# Translators.net
KiCad netlist of a schematic drawn in Altium Designer
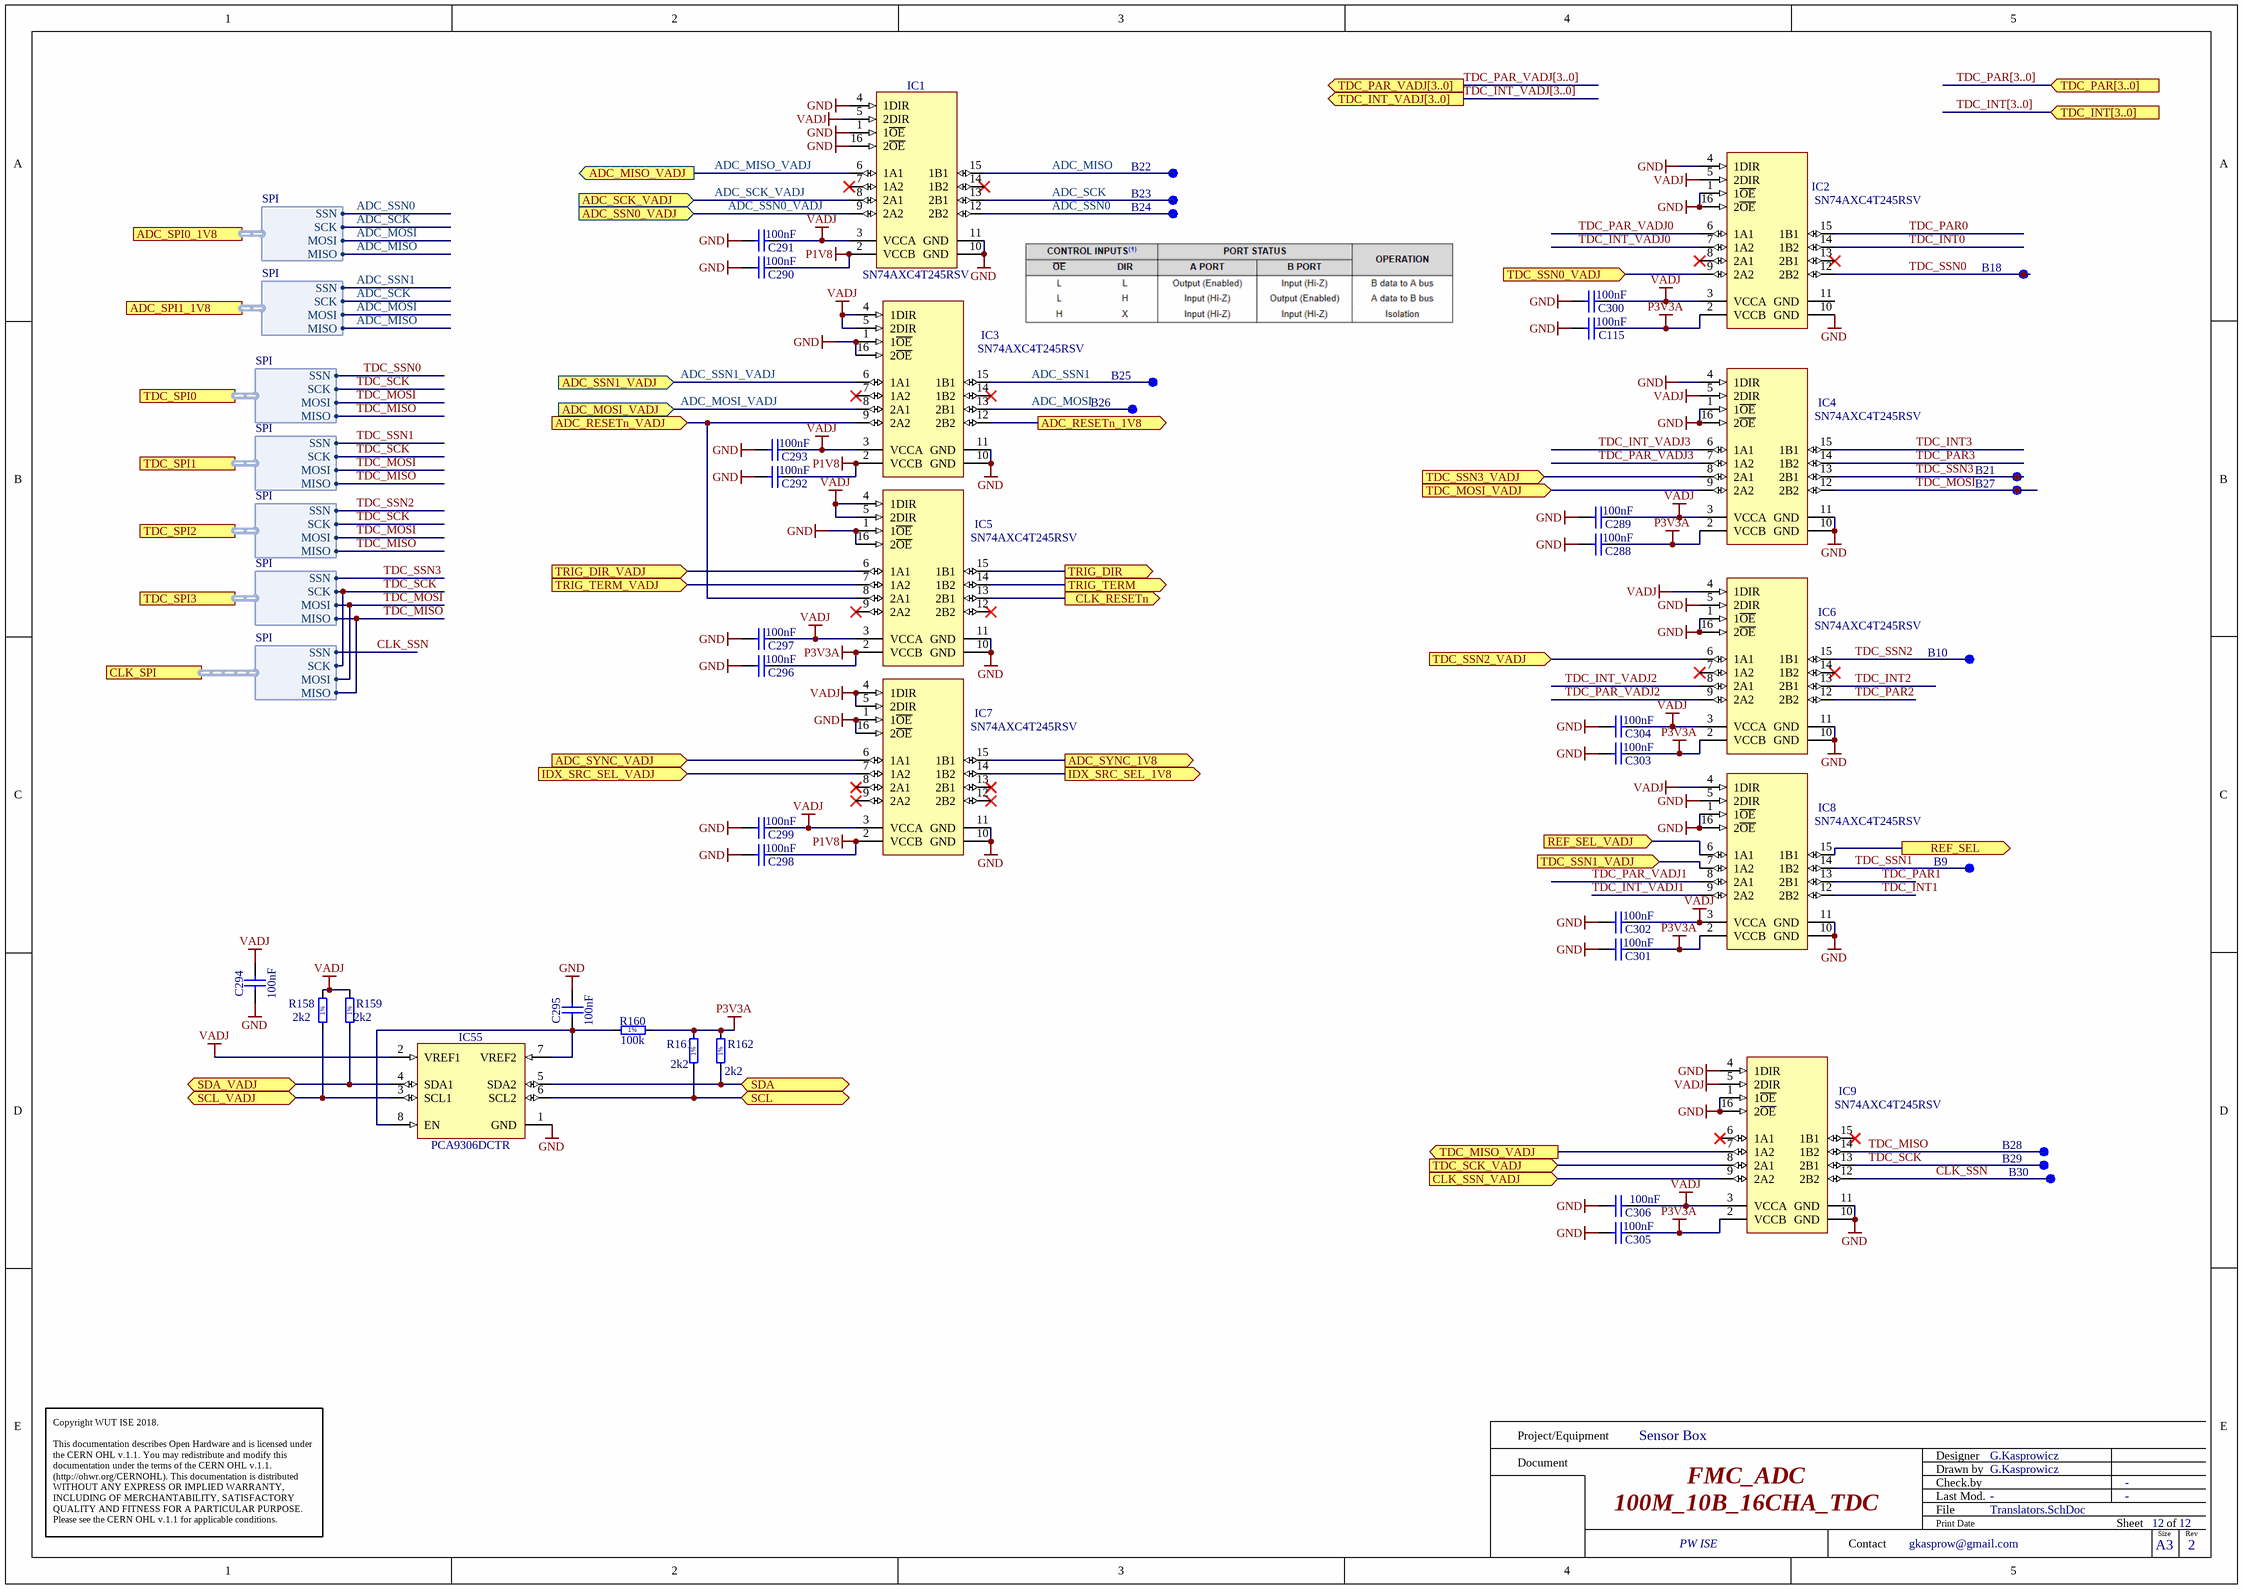
[diagram p0: Translators.SchDoc]

(export (version "E")
  (design (tool "Eeschema 10.0.6"))
  (components
    (comp (ref "B9")
      (value "SMD Pad")
      (footprint "C100")
      (description "Through Hole Pad")
      (fields (field (name "PART NUMBER") "SMD_PAD_D1MM") (field (name "AUTHOR") "CERN DEM JLC"))
      (libsource (lib "Eletro-mechanical") (part "Single SMD Pad (Round)"))
    )
    (comp (ref "B10")
      (value "SMD Pad")
      (footprint "C100")
      (description "Through Hole Pad")
      (fields (field (name "PART NUMBER") "SMD_PAD_D1MM") (field (name "AUTHOR") "CERN DEM JLC"))
      (libsource (lib "Eletro-mechanical") (part "Single SMD Pad (Round)"))
    )
    (comp (ref "B18")
      (value "SMD Pad")
      (footprint "C100")
      (description "Through Hole Pad")
      (fields (field (name "PART NUMBER") "SMD_PAD_D1MM") (field (name "AUTHOR") "CERN DEM JLC"))
      (libsource (lib "Eletro-mechanical") (part "Single SMD Pad (Round)"))
    )
    (comp (ref "B21")
      (value "SMD Pad")
      (footprint "C100")
      (description "Through Hole Pad")
      (fields (field (name "PART NUMBER") "SMD_PAD_D1MM") (field (name "AUTHOR") "CERN DEM JLC"))
      (libsource (lib "Eletro-mechanical") (part "Single SMD Pad (Round)"))
    )
    (comp (ref "B22")
      (value "SMD Pad")
      (footprint "C100")
      (description "Through Hole Pad")
      (fields (field (name "PART NUMBER") "SMD_PAD_D1MM") (field (name "AUTHOR") "CERN DEM JLC"))
      (libsource (lib "Eletro-mechanical") (part "Single SMD Pad (Round)"))
    )
    (comp (ref "B23")
      (value "SMD Pad")
      (footprint "C100")
      (description "Through Hole Pad")
      (fields (field (name "PART NUMBER") "SMD_PAD_D1MM") (field (name "AUTHOR") "CERN DEM JLC"))
      (libsource (lib "Eletro-mechanical") (part "Single SMD Pad (Round)"))
    )
    (comp (ref "B24")
      (value "SMD Pad")
      (footprint "C100")
      (description "Through Hole Pad")
      (fields (field (name "PART NUMBER") "SMD_PAD_D1MM") (field (name "AUTHOR") "CERN DEM JLC"))
      (libsource (lib "Eletro-mechanical") (part "Single SMD Pad (Round)"))
    )
    (comp (ref "B25")
      (value "SMD Pad")
      (footprint "C100")
      (description "Through Hole Pad")
      (fields (field (name "PART NUMBER") "SMD_PAD_D1MM") (field (name "AUTHOR") "CERN DEM JLC"))
      (libsource (lib "Eletro-mechanical") (part "Single SMD Pad (Round)"))
    )
    (comp (ref "B26")
      (value "SMD Pad")
      (footprint "C100")
      (description "Through Hole Pad")
      (fields (field (name "PART NUMBER") "SMD_PAD_D1MM") (field (name "AUTHOR") "CERN DEM JLC"))
      (libsource (lib "Eletro-mechanical") (part "Single SMD Pad (Round)"))
    )
    (comp (ref "B27")
      (value "SMD Pad")
      (footprint "C100")
      (description "Through Hole Pad")
      (fields (field (name "PART NUMBER") "SMD_PAD_D1MM") (field (name "AUTHOR") "CERN DEM JLC"))
      (libsource (lib "Eletro-mechanical") (part "Single SMD Pad (Round)"))
    )
    (comp (ref "B28")
      (value "SMD Pad")
      (footprint "C100")
      (description "Through Hole Pad")
      (fields (field (name "PART NUMBER") "SMD_PAD_D1MM") (field (name "AUTHOR") "CERN DEM JLC"))
      (libsource (lib "Eletro-mechanical") (part "Single SMD Pad (Round)"))
    )
    (comp (ref "B29")
      (value "SMD Pad")
      (footprint "C100")
      (description "Through Hole Pad")
      (fields (field (name "PART NUMBER") "SMD_PAD_D1MM") (field (name "AUTHOR") "CERN DEM JLC"))
      (libsource (lib "Eletro-mechanical") (part "Single SMD Pad (Round)"))
    )
    (comp (ref "B30")
      (value "SMD Pad")
      (footprint "C100")
      (description "Through Hole Pad")
      (fields (field (name "PART NUMBER") "SMD_PAD_D1MM") (field (name "AUTHOR") "CERN DEM JLC"))
      (libsource (lib "Eletro-mechanical") (part "Single SMD Pad (Round)"))
    )
    (comp (ref "C115")
      (value "100nF")
      (footprint "CAPC0603X33N")
      (description "Non-polarised capacitor")
      (fields
        (field (name "MANUFACTURER PART NUMBER") "CC0201_100NF_6.3V_10%_X5R")
        (field (name "MANUFACTURER") "GENERIC")
        (field (name "AUTHOR") "CERN DEM JLC")
      )
      (libsource (lib "Capacitors") (part "Capacitor - non polarized"))
    )
    (comp (ref "C288")
      (value "100nF")
      (footprint "CAPC0603X33N")
      (description "Non-polarised capacitor")
      (fields
        (field (name "MANUFACTURER PART NUMBER") "CC0201_100NF_6.3V_10%_X5R")
        (field (name "MANUFACTURER") "GENERIC")
        (field (name "AUTHOR") "CERN DEM JLC")
      )
      (libsource (lib "Capacitors") (part "Capacitor - non polarized"))
    )
    (comp (ref "C289")
      (value "100nF")
      (footprint "CAPC0603X33N")
      (description "Non-polarised capacitor")
      (fields
        (field (name "MANUFACTURER PART NUMBER") "CC0201_100NF_6.3V_10%_X5R")
        (field (name "MANUFACTURER") "GENERIC")
        (field (name "AUTHOR") "CERN DEM JLC")
      )
      (libsource (lib "Capacitors") (part "Capacitor - non polarized"))
    )
    (comp (ref "C290")
      (value "100nF")
      (footprint "CAPC0603X33N")
      (description "Non-polarised capacitor")
      (fields
        (field (name "MANUFACTURER PART NUMBER") "CC0201_100NF_6.3V_10%_X5R")
        (field (name "MANUFACTURER") "GENERIC")
        (field (name "AUTHOR") "CERN DEM JLC")
      )
      (libsource (lib "Capacitors") (part "Capacitor - non polarized"))
    )
    (comp (ref "C291")
      (value "100nF")
      (footprint "CAPC0603X33N")
      (description "Non-polarised capacitor")
      (fields
        (field (name "MANUFACTURER PART NUMBER") "CC0201_100NF_6.3V_10%_X5R")
        (field (name "MANUFACTURER") "GENERIC")
        (field (name "AUTHOR") "CERN DEM JLC")
      )
      (libsource (lib "Capacitors") (part "Capacitor - non polarized"))
    )
    (comp (ref "C292")
      (value "100nF")
      (footprint "CAPC0603X33N")
      (description "Non-polarised capacitor")
      (fields
        (field (name "MANUFACTURER PART NUMBER") "CC0201_100NF_6.3V_10%_X5R")
        (field (name "MANUFACTURER") "GENERIC")
        (field (name "AUTHOR") "CERN DEM JLC")
      )
      (libsource (lib "Capacitors") (part "Capacitor - non polarized"))
    )
    (comp (ref "C293")
      (value "100nF")
      (footprint "CAPC0603X33N")
      (description "Non-polarised capacitor")
      (fields
        (field (name "MANUFACTURER PART NUMBER") "CC0201_100NF_6.3V_10%_X5R")
        (field (name "MANUFACTURER") "GENERIC")
        (field (name "AUTHOR") "CERN DEM JLC")
      )
      (libsource (lib "Capacitors") (part "Capacitor - non polarized"))
    )
    (comp (ref "C294")
      (value "100nF")
      (footprint "CAPC0603X33N")
      (description "Non-polarised capacitor")
      (fields
        (field (name "MANUFACTURER PART NUMBER") "CC0201_100NF_6.3V_10%_X5R")
        (field (name "MANUFACTURER") "GENERIC")
        (field (name "AUTHOR") "CERN DEM JLC")
      )
      (libsource (lib "Capacitors") (part "Capacitor - non polarized"))
    )
    (comp (ref "C295")
      (value "100nF")
      (footprint "CAPC0603X33N")
      (description "Non-polarised capacitor")
      (fields
        (field (name "MANUFACTURER PART NUMBER") "CC0201_100NF_6.3V_10%_X5R")
        (field (name "MANUFACTURER") "GENERIC")
        (field (name "AUTHOR") "CERN DEM JLC")
      )
      (libsource (lib "Capacitors") (part "Capacitor - non polarized"))
    )
    (comp (ref "C296")
      (value "100nF")
      (footprint "CAPC0603X33N")
      (description "Non-polarised capacitor")
      (fields
        (field (name "MANUFACTURER PART NUMBER") "CC0201_100NF_6.3V_10%_X5R")
        (field (name "MANUFACTURER") "GENERIC")
        (field (name "AUTHOR") "CERN DEM JLC")
      )
      (libsource (lib "Capacitors") (part "Capacitor - non polarized"))
    )
    (comp (ref "C297")
      (value "100nF")
      (footprint "CAPC0603X33N")
      (description "Non-polarised capacitor")
      (fields
        (field (name "MANUFACTURER PART NUMBER") "CC0201_100NF_6.3V_10%_X5R")
        (field (name "MANUFACTURER") "GENERIC")
        (field (name "AUTHOR") "CERN DEM JLC")
      )
      (libsource (lib "Capacitors") (part "Capacitor - non polarized"))
    )
    (comp (ref "C298")
      (value "100nF")
      (footprint "CAPC0603X33N")
      (description "Non-polarised capacitor")
      (fields
        (field (name "MANUFACTURER PART NUMBER") "CC0201_100NF_6.3V_10%_X5R")
        (field (name "MANUFACTURER") "GENERIC")
        (field (name "AUTHOR") "CERN DEM JLC")
      )
      (libsource (lib "Capacitors") (part "Capacitor - non polarized"))
    )
    (comp (ref "C299")
      (value "100nF")
      (footprint "CAPC0603X33N")
      (description "Non-polarised capacitor")
      (fields
        (field (name "MANUFACTURER PART NUMBER") "CC0201_100NF_6.3V_10%_X5R")
        (field (name "MANUFACTURER") "GENERIC")
        (field (name "AUTHOR") "CERN DEM JLC")
      )
      (libsource (lib "Capacitors") (part "Capacitor - non polarized"))
    )
    (comp (ref "C300")
      (value "100nF")
      (footprint "CAPC0603X33N")
      (description "Non-polarised capacitor")
      (fields
        (field (name "MANUFACTURER PART NUMBER") "CC0201_100NF_6.3V_10%_X5R")
        (field (name "MANUFACTURER") "GENERIC")
        (field (name "AUTHOR") "CERN DEM JLC")
      )
      (libsource (lib "Capacitors") (part "Capacitor - non polarized"))
    )
    (comp (ref "C301")
      (value "100nF")
      (footprint "CAPC0603X33N")
      (description "Non-polarised capacitor")
      (fields
        (field (name "MANUFACTURER PART NUMBER") "CC0201_100NF_6.3V_10%_X5R")
        (field (name "MANUFACTURER") "GENERIC")
        (field (name "AUTHOR") "CERN DEM JLC")
      )
      (libsource (lib "Capacitors") (part "Capacitor - non polarized"))
    )
    (comp (ref "C302")
      (value "100nF")
      (footprint "CAPC0603X33N")
      (description "Non-polarised capacitor")
      (fields
        (field (name "MANUFACTURER PART NUMBER") "CC0201_100NF_6.3V_10%_X5R")
        (field (name "MANUFACTURER") "GENERIC")
        (field (name "AUTHOR") "CERN DEM JLC")
      )
      (libsource (lib "Capacitors") (part "Capacitor - non polarized"))
    )
    (comp (ref "C303")
      (value "100nF")
      (footprint "CAPC0603X33N")
      (description "Non-polarised capacitor")
      (fields
        (field (name "MANUFACTURER PART NUMBER") "CC0201_100NF_6.3V_10%_X5R")
        (field (name "MANUFACTURER") "GENERIC")
        (field (name "AUTHOR") "CERN DEM JLC")
      )
      (libsource (lib "Capacitors") (part "Capacitor - non polarized"))
    )
    (comp (ref "C304")
      (value "100nF")
      (footprint "CAPC0603X33N")
      (description "Non-polarised capacitor")
      (fields
        (field (name "MANUFACTURER PART NUMBER") "CC0201_100NF_6.3V_10%_X5R")
        (field (name "MANUFACTURER") "GENERIC")
        (field (name "AUTHOR") "CERN DEM JLC")
      )
      (libsource (lib "Capacitors") (part "Capacitor - non polarized"))
    )
    (comp (ref "C305")
      (value "100nF")
      (footprint "CAPC0603X33N")
      (description "Non-polarised capacitor")
      (fields
        (field (name "MANUFACTURER PART NUMBER") "CC0201_100NF_6.3V_10%_X5R")
        (field (name "MANUFACTURER") "GENERIC")
        (field (name "AUTHOR") "CERN DEM JLC")
      )
      (libsource (lib "Capacitors") (part "Capacitor - non polarized"))
    )
    (comp (ref "C306")
      (value "100nF")
      (footprint "CAPC0603X33N")
      (description "Non-polarised capacitor")
      (fields
        (field (name "MANUFACTURER PART NUMBER") "CC0201_100NF_6.3V_10%_X5R")
        (field (name "MANUFACTURER") "GENERIC")
        (field (name "AUTHOR") "CERN DEM JLC")
      )
      (libsource (lib "Capacitors") (part "Capacitor - non polarized"))
    )
    (comp (ref "IC1")
      (value "SN74AXC4T245RSV")
      (footprint "QFN40P180X260X55-16N")
      (description "4-Bit Dual-Supply Bus Transceiver with Configurable Voltage Translation and 3-State Output")
      (fields (field (name "MANUFACTURER") "TEXAS INSTRUMENTS") (field (name "AUTHOR") "GK"))
      (libsource (lib "ICS-logic") (part "SN74AXC4T245"))
    )
    (comp (ref "IC2")
      (value "SN74AXC4T245RSV")
      (footprint "QFN40P180X260X55-16N")
      (description "4-Bit Dual-Supply Bus Transceiver with Configurable Voltage Translation and 3-State Output")
      (fields (field (name "MANUFACTURER") "TEXAS INSTRUMENTS") (field (name "AUTHOR") "GK"))
      (libsource (lib "ICS-logic") (part "SN74AXC4T245"))
    )
    (comp (ref "IC3")
      (value "SN74AXC4T245RSV")
      (footprint "QFN40P180X260X55-16N")
      (description "4-Bit Dual-Supply Bus Transceiver with Configurable Voltage Translation and 3-State Output")
      (fields (field (name "MANUFACTURER") "TEXAS INSTRUMENTS") (field (name "AUTHOR") "GK"))
      (libsource (lib "ICS-logic") (part "SN74AXC4T245"))
    )
    (comp (ref "IC4")
      (value "SN74AXC4T245RSV")
      (footprint "QFN40P180X260X55-16N")
      (description "4-Bit Dual-Supply Bus Transceiver with Configurable Voltage Translation and 3-State Output")
      (fields (field (name "MANUFACTURER") "TEXAS INSTRUMENTS") (field (name "AUTHOR") "GK"))
      (libsource (lib "ICS-logic") (part "SN74AXC4T245"))
    )
    (comp (ref "IC5")
      (value "SN74AXC4T245RSV")
      (footprint "QFN40P180X260X55-16N")
      (description "4-Bit Dual-Supply Bus Transceiver with Configurable Voltage Translation and 3-State Output")
      (fields (field (name "MANUFACTURER") "TEXAS INSTRUMENTS") (field (name "AUTHOR") "GK"))
      (libsource (lib "ICS-logic") (part "SN74AXC4T245"))
    )
    (comp (ref "IC6")
      (value "SN74AXC4T245RSV")
      (footprint "QFN40P180X260X55-16N")
      (description "4-Bit Dual-Supply Bus Transceiver with Configurable Voltage Translation and 3-State Output")
      (fields (field (name "MANUFACTURER") "TEXAS INSTRUMENTS") (field (name "AUTHOR") "GK"))
      (libsource (lib "ICS-logic") (part "SN74AXC4T245"))
    )
    (comp (ref "IC7")
      (value "SN74AXC4T245RSV")
      (footprint "QFN40P180X260X55-16N")
      (description "4-Bit Dual-Supply Bus Transceiver with Configurable Voltage Translation and 3-State Output")
      (fields (field (name "MANUFACTURER") "TEXAS INSTRUMENTS") (field (name "AUTHOR") "GK"))
      (libsource (lib "ICS-logic") (part "SN74AXC4T245"))
    )
    (comp (ref "IC8")
      (value "SN74AXC4T245RSV")
      (footprint "QFN40P180X260X55-16N")
      (description "4-Bit Dual-Supply Bus Transceiver with Configurable Voltage Translation and 3-State Output")
      (fields (field (name "MANUFACTURER") "TEXAS INSTRUMENTS") (field (name "AUTHOR") "GK"))
      (libsource (lib "ICS-logic") (part "SN74AXC4T245"))
    )
    (comp (ref "IC9")
      (value "SN74AXC4T245RSV")
      (footprint "QFN40P180X260X55-16N")
      (description "4-Bit Dual-Supply Bus Transceiver with Configurable Voltage Translation and 3-State Output")
      (fields (field (name "MANUFACTURER") "TEXAS INSTRUMENTS") (field (name "AUTHOR") "GK"))
      (libsource (lib "ICS-logic") (part "SN74AXC4T245"))
    )
    (comp (ref "IC55")
      (value "PCA9306DCTR")
      (footprint "SOP65P400X130-8N")
      (description "Dual Bidirectional I2C Bus And SMBus Voltage-Level Translator")
      (fields (field (name "MANUFACTURER") "TEXAS INSTRUMENTS") (field (name "AUTHOR") "CERN DEM JLC"))
      (libsource (lib "ICs And Semiconductors") (part "PCA9306DC"))
    )
    (comp (ref "R158")
      (value "2k2")
      (footprint "RESC1005X40N")
      (description "Resistor - 1%")
      (fields
        (field (name "PART NUMBER") "R0402_2K2_1%_0.0625W_100PPM")
        (field (name "POWER") "0.0625W")
        (field (name "AUTHOR") "CERN DEM JLC")
      )
      (libsource (lib "Resistors") (part "Resistor - 1%"))
    )
    (comp (ref "R159")
      (value "2k2")
      (footprint "RESC1005X40N")
      (description "Resistor - 1%")
      (fields
        (field (name "PART NUMBER") "R0402_2K2_1%_0.0625W_100PPM")
        (field (name "POWER") "0.0625W")
        (field (name "AUTHOR") "CERN DEM JLC")
      )
      (libsource (lib "Resistors") (part "Resistor - 1%"))
    )
    (comp (ref "R160")
      (value "100k")
      (footprint "RESC1005X40N")
      (description "Resistor - 1%")
      (fields
        (field (name "PART NUMBER") "R0402_100K_1%_0.0625W_100PPM")
        (field (name "POWER") "0.0625W")
        (field (name "AUTHOR") "CERN DEM JLC")
      )
      (libsource (lib "Resistors") (part "Resistor - 1%"))
    )
    (comp (ref "R161")
      (value "2k2")
      (footprint "RESC1005X40N")
      (description "Resistor - 1%")
      (fields
        (field (name "PART NUMBER") "R0402_2K2_1%_0.0625W_100PPM")
        (field (name "POWER") "0.0625W")
        (field (name "AUTHOR") "CERN DEM JLC")
      )
      (libsource (lib "Resistors") (part "Resistor - 1%"))
    )
    (comp (ref "R162")
      (value "2k2")
      (footprint "RESC1005X40N")
      (description "Resistor - 1%")
      (fields
        (field (name "PART NUMBER") "R0402_2K2_1%_0.0625W_100PPM")
        (field (name "POWER") "0.0625W")
        (field (name "AUTHOR") "CERN DEM JLC")
      )
      (libsource (lib "Resistors") (part "Resistor - 1%"))
    )
  )
  (nets
    (net (code "2") (name "/ADC_MISO") (class "Default")
      (node (ref "B22") (pin "1") (pinfunction "1_1") (pintype "bidirectional"))
      (node (ref "IC1") (pin "15") (pinfunction "1B1_15") (pintype "bidirectional"))
    )
    (net (code "3") (name "/ADC_MISO_VADJ") (class "Default")
      (node (ref "IC1") (pin "6") (pinfunction "1A1_6") (pintype "bidirectional"))
    )
    (net (code "4") (name "/ADC_MOSI") (class "Default")
      (node (ref "B26") (pin "1") (pinfunction "1_1") (pintype "bidirectional"))
      (node (ref "IC3") (pin "13") (pinfunction "2B1_13") (pintype "bidirectional"))
    )
    (net (code "5") (name "/ADC_MOSI_VADJ") (class "Default")
      (node (ref "IC3") (pin "8") (pinfunction "2A1_8") (pintype "bidirectional"))
    )
    (net (code "6") (name "/ADC_RESETn_1V8") (class "Default")
      (node (ref "IC3") (pin "12") (pinfunction "2B2_12") (pintype "bidirectional"))
    )
    (net (code "7") (name "/ADC_RESETn_VADJ") (class "Default")
      (node (ref "IC3") (pin "9") (pinfunction "2A2_9") (pintype "bidirectional"))
      (node (ref "IC5") (pin "8") (pinfunction "2A1_8") (pintype "bidirectional"))
    )
    (net (code "8") (name "/ADC_SCK") (class "Default")
      (node (ref "B23") (pin "1") (pinfunction "1_1") (pintype "bidirectional"))
      (node (ref "IC1") (pin "13") (pinfunction "2B1_13") (pintype "bidirectional"))
    )
    (net (code "9") (name "/ADC_SCK_VADJ") (class "Default")
      (node (ref "IC1") (pin "8") (pinfunction "2A1_8") (pintype "bidirectional"))
    )
    (net (code "10") (name "/ADC_SSN0") (class "Default")
      (node (ref "B24") (pin "1") (pinfunction "1_1") (pintype "bidirectional"))
      (node (ref "IC1") (pin "12") (pinfunction "2B2_12") (pintype "bidirectional"))
    )
    (net (code "11") (name "/ADC_SSN0_VADJ") (class "Default")
      (node (ref "IC1") (pin "9") (pinfunction "2A2_9") (pintype "bidirectional"))
    )
    (net (code "12") (name "/ADC_SSN1") (class "Default")
      (node (ref "B25") (pin "1") (pinfunction "1_1") (pintype "bidirectional"))
      (node (ref "IC3") (pin "15") (pinfunction "1B1_15") (pintype "bidirectional"))
    )
    (net (code "13") (name "/ADC_SSN1_VADJ") (class "Default")
      (node (ref "IC3") (pin "6") (pinfunction "1A1_6") (pintype "bidirectional"))
    )
    (net (code "14") (name "/ADC_SYNC_1V8") (class "Default")
      (node (ref "IC7") (pin "15") (pinfunction "1B1_15") (pintype "bidirectional"))
    )
    (net (code "15") (name "/ADC_SYNC_VADJ") (class "Default")
      (node (ref "IC7") (pin "6") (pinfunction "1A1_6") (pintype "bidirectional"))
    )
    (net (code "16") (name "/CLK_RESETn") (class "Default")
      (node (ref "IC5") (pin "13") (pinfunction "2B1_13") (pintype "bidirectional"))
    )
    (net (code "17") (name "/CLK_SSN") (class "Default")
      (node (ref "B30") (pin "1") (pinfunction "1_1") (pintype "bidirectional"))
      (node (ref "IC9") (pin "12") (pinfunction "2B2_12") (pintype "bidirectional"))
    )
    (net (code "18") (name "/CLK_SSN_VADJ") (class "Default")
      (node (ref "IC9") (pin "9") (pinfunction "2A2_9") (pintype "bidirectional"))
    )
    (net (code "19") (name "/IDX_SRC_SEL_1V8") (class "Default")
      (node (ref "IC7") (pin "14") (pinfunction "1B2_14") (pintype "bidirectional"))
    )
    (net (code "20") (name "/IDX_SRC_SEL_VADJ") (class "Default")
      (node (ref "IC7") (pin "7") (pinfunction "1A2_7") (pintype "bidirectional"))
    )
    (net (code "21") (name "/REF_SEL") (class "Default")
      (node (ref "IC8") (pin "15") (pinfunction "1B1_15") (pintype "bidirectional"))
    )
    (net (code "22") (name "/REF_SEL_VADJ") (class "Default")
      (node (ref "IC8") (pin "6") (pinfunction "1A1_6") (pintype "bidirectional"))
    )
    (net (code "23") (name "/SCL") (class "Default")
      (node (ref "IC55") (pin "6") (pinfunction "SCL2_6") (pintype "bidirectional"))
      (node (ref "R161") (pin "1") (pinfunction "1_1") (pintype "passive"))
    )
    (net (code "24") (name "/SCL_VADJ") (class "Default")
      (node (ref "IC55") (pin "3") (pinfunction "SCL1_3") (pintype "bidirectional"))
      (node (ref "R158") (pin "1") (pinfunction "1_1") (pintype "passive"))
    )
    (net (code "25") (name "/SDA") (class "Default")
      (node (ref "IC55") (pin "5") (pinfunction "SDA2_5") (pintype "bidirectional"))
      (node (ref "R162") (pin "1") (pinfunction "1_1") (pintype "passive"))
    )
    (net (code "26") (name "/SDA_VADJ") (class "Default")
      (node (ref "IC55") (pin "4") (pinfunction "SDA1_4") (pintype "bidirectional"))
      (node (ref "R159") (pin "1") (pinfunction "1_1") (pintype "passive"))
    )
    (net (code "27") (name "/TDC_INT0") (class "Default")
      (node (ref "IC2") (pin "14") (pinfunction "1B2_14") (pintype "bidirectional"))
    )
    (net (code "28") (name "/TDC_INT1") (class "Default")
      (node (ref "IC8") (pin "12") (pinfunction "2B2_12") (pintype "bidirectional"))
    )
    (net (code "29") (name "/TDC_INT2") (class "Default")
      (node (ref "IC6") (pin "13") (pinfunction "2B1_13") (pintype "bidirectional"))
    )
    (net (code "30") (name "/TDC_INT3") (class "Default")
      (node (ref "IC4") (pin "15") (pinfunction "1B1_15") (pintype "bidirectional"))
    )
    (net (code "32") (name "/TDC_INT_VADJ0") (class "Default")
      (node (ref "IC2") (pin "7") (pinfunction "1A2_7") (pintype "bidirectional"))
    )
    (net (code "33") (name "/TDC_INT_VADJ1") (class "Default")
      (node (ref "IC8") (pin "9") (pinfunction "2A2_9") (pintype "bidirectional"))
    )
    (net (code "34") (name "/TDC_INT_VADJ2") (class "Default")
      (node (ref "IC6") (pin "8") (pinfunction "2A1_8") (pintype "bidirectional"))
    )
    (net (code "35") (name "/TDC_INT_VADJ3") (class "Default")
      (node (ref "IC4") (pin "6") (pinfunction "1A1_6") (pintype "bidirectional"))
    )
    (net (code "37") (name "/TDC_MISO") (class "Default")
      (node (ref "B28") (pin "1") (pinfunction "1_1") (pintype "bidirectional"))
      (node (ref "IC9") (pin "14") (pinfunction "1B2_14") (pintype "bidirectional"))
    )
    (net (code "38") (name "/TDC_MISO_VADJ") (class "Default")
      (node (ref "IC9") (pin "7") (pinfunction "1A2_7") (pintype "bidirectional"))
    )
    (net (code "39") (name "/TDC_MOSI") (class "Default")
      (node (ref "B27") (pin "1") (pinfunction "1_1") (pintype "bidirectional"))
      (node (ref "IC4") (pin "12") (pinfunction "2B2_12") (pintype "bidirectional"))
    )
    (net (code "40") (name "/TDC_MOSI_VADJ") (class "Default")
      (node (ref "IC4") (pin "9") (pinfunction "2A2_9") (pintype "bidirectional"))
    )
    (net (code "41") (name "/TDC_PAR0") (class "Default")
      (node (ref "IC2") (pin "15") (pinfunction "1B1_15") (pintype "bidirectional"))
    )
    (net (code "42") (name "/TDC_PAR1") (class "Default")
      (node (ref "IC8") (pin "13") (pinfunction "2B1_13") (pintype "bidirectional"))
    )
    (net (code "43") (name "/TDC_PAR2") (class "Default")
      (node (ref "IC6") (pin "12") (pinfunction "2B2_12") (pintype "bidirectional"))
    )
    (net (code "44") (name "/TDC_PAR3") (class "Default")
      (node (ref "IC4") (pin "14") (pinfunction "1B2_14") (pintype "bidirectional"))
    )
    (net (code "46") (name "/TDC_PAR_VADJ0") (class "Default")
      (node (ref "IC2") (pin "6") (pinfunction "1A1_6") (pintype "bidirectional"))
    )
    (net (code "47") (name "/TDC_PAR_VADJ1") (class "Default")
      (node (ref "IC8") (pin "8") (pinfunction "2A1_8") (pintype "bidirectional"))
    )
    (net (code "48") (name "/TDC_PAR_VADJ2") (class "Default")
      (node (ref "IC6") (pin "9") (pinfunction "2A2_9") (pintype "bidirectional"))
    )
    (net (code "49") (name "/TDC_PAR_VADJ3") (class "Default")
      (node (ref "IC4") (pin "7") (pinfunction "1A2_7") (pintype "bidirectional"))
    )
    (net (code "51") (name "/TDC_SCK") (class "Default")
      (node (ref "B29") (pin "1") (pinfunction "1_1") (pintype "bidirectional"))
      (node (ref "IC9") (pin "13") (pinfunction "2B1_13") (pintype "bidirectional"))
    )
    (net (code "52") (name "/TDC_SCK_VADJ") (class "Default")
      (node (ref "IC9") (pin "8") (pinfunction "2A1_8") (pintype "bidirectional"))
    )
    (net (code "53") (name "/TDC_SSN0") (class "Default")
      (node (ref "B18") (pin "1") (pinfunction "1_1") (pintype "bidirectional"))
      (node (ref "IC2") (pin "12") (pinfunction "2B2_12") (pintype "bidirectional"))
    )
    (net (code "54") (name "/TDC_SSN0_VADJ") (class "Default")
      (node (ref "IC2") (pin "9") (pinfunction "2A2_9") (pintype "bidirectional"))
    )
    (net (code "55") (name "/TDC_SSN1") (class "Default")
      (node (ref "B9") (pin "1") (pinfunction "1_1") (pintype "bidirectional"))
      (node (ref "IC8") (pin "14") (pinfunction "1B2_14") (pintype "bidirectional"))
    )
    (net (code "56") (name "/TDC_SSN1_VADJ") (class "Default")
      (node (ref "IC8") (pin "7") (pinfunction "1A2_7") (pintype "bidirectional"))
    )
    (net (code "57") (name "/TDC_SSN2") (class "Default")
      (node (ref "B10") (pin "1") (pinfunction "1_1") (pintype "bidirectional"))
      (node (ref "IC6") (pin "15") (pinfunction "1B1_15") (pintype "bidirectional"))
    )
    (net (code "58") (name "/TDC_SSN2_VADJ") (class "Default")
      (node (ref "IC6") (pin "6") (pinfunction "1A1_6") (pintype "bidirectional"))
    )
    (net (code "59") (name "/TDC_SSN3") (class "Default")
      (node (ref "B21") (pin "1") (pinfunction "1_1") (pintype "bidirectional"))
      (node (ref "IC4") (pin "13") (pinfunction "2B1_13") (pintype "bidirectional"))
    )
    (net (code "60") (name "/TDC_SSN3_VADJ") (class "Default")
      (node (ref "IC4") (pin "8") (pinfunction "2A1_8") (pintype "bidirectional"))
    )
    (net (code "61") (name "/TRIG_DIR") (class "Default")
      (node (ref "IC5") (pin "15") (pinfunction "1B1_15") (pintype "bidirectional"))
    )
    (net (code "62") (name "/TRIG_DIR_VADJ") (class "Default")
      (node (ref "IC5") (pin "6") (pinfunction "1A1_6") (pintype "bidirectional"))
    )
    (net (code "63") (name "/TRIG_TERM") (class "Default")
      (node (ref "IC5") (pin "14") (pinfunction "1B2_14") (pintype "bidirectional"))
    )
    (net (code "64") (name "/TRIG_TERM_VADJ") (class "Default")
      (node (ref "IC5") (pin "7") (pinfunction "1A2_7") (pintype "bidirectional"))
    )
    (net (code "66") (name "GND") (class "Default")
      (node (ref "C115") (pin "2") (pinfunction "2_2") (pintype "passive"))
      (node (ref "C288") (pin "2") (pinfunction "2_2") (pintype "passive"))
      (node (ref "C289") (pin "2") (pinfunction "2_2") (pintype "passive"))
      (node (ref "C290") (pin "2") (pinfunction "2_2") (pintype "passive"))
      (node (ref "C291") (pin "2") (pinfunction "2_2") (pintype "passive"))
      (node (ref "C292") (pin "2") (pinfunction "2_2") (pintype "passive"))
      (node (ref "C293") (pin "2") (pinfunction "2_2") (pintype "passive"))
      (node (ref "C294") (pin "1") (pinfunction "1_1") (pintype "passive"))
      (node (ref "C295") (pin "2") (pinfunction "2_2") (pintype "passive"))
      (node (ref "C296") (pin "2") (pinfunction "2_2") (pintype "passive"))
      (node (ref "C297") (pin "2") (pinfunction "2_2") (pintype "passive"))
      (node (ref "C298") (pin "2") (pinfunction "2_2") (pintype "passive"))
      (node (ref "C299") (pin "2") (pinfunction "2_2") (pintype "passive"))
      (node (ref "C300") (pin "2") (pinfunction "2_2") (pintype "passive"))
      (node (ref "C301") (pin "2") (pinfunction "2_2") (pintype "passive"))
      (node (ref "C302") (pin "2") (pinfunction "2_2") (pintype "passive"))
      (node (ref "C303") (pin "2") (pinfunction "2_2") (pintype "passive"))
      (node (ref "C304") (pin "2") (pinfunction "2_2") (pintype "passive"))
      (node (ref "C305") (pin "2") (pinfunction "2_2") (pintype "passive"))
      (node (ref "C306") (pin "2") (pinfunction "2_2") (pintype "passive"))
      (node (ref "IC1") (pin "1") (pinfunction "1~{OE}_1") (pintype "input"))
      (node (ref "IC1") (pin "10") (pinfunction "GND_10") (pintype "power_in"))
      (node (ref "IC1") (pin "11") (pinfunction "GND_11") (pintype "power_in"))
      (node (ref "IC1") (pin "16") (pinfunction "2~{OE}_16") (pintype "input"))
      (node (ref "IC1") (pin "4") (pinfunction "1DIR_4") (pintype "input"))
      (node (ref "IC2") (pin "1") (pinfunction "1~{OE}_1") (pintype "input"))
      (node (ref "IC2") (pin "10") (pinfunction "GND_10") (pintype "power_in"))
      (node (ref "IC2") (pin "16") (pinfunction "2~{OE}_16") (pintype "input"))
      (node (ref "IC2") (pin "4") (pinfunction "1DIR_4") (pintype "input"))
      (node (ref "IC3") (pin "1") (pinfunction "1~{OE}_1") (pintype "input"))
      (node (ref "IC3") (pin "10") (pinfunction "GND_10") (pintype "power_in"))
      (node (ref "IC3") (pin "11") (pinfunction "GND_11") (pintype "power_in"))
      (node (ref "IC3") (pin "16") (pinfunction "2~{OE}_16") (pintype "input"))
      (node (ref "IC4") (pin "1") (pinfunction "1~{OE}_1") (pintype "input"))
      (node (ref "IC4") (pin "10") (pinfunction "GND_10") (pintype "power_in"))
      (node (ref "IC4") (pin "11") (pinfunction "GND_11") (pintype "power_in"))
      (node (ref "IC4") (pin "16") (pinfunction "2~{OE}_16") (pintype "input"))
      (node (ref "IC4") (pin "4") (pinfunction "1DIR_4") (pintype "input"))
      (node (ref "IC5") (pin "1") (pinfunction "1~{OE}_1") (pintype "input"))
      (node (ref "IC5") (pin "10") (pinfunction "GND_10") (pintype "power_in"))
      (node (ref "IC5") (pin "11") (pinfunction "GND_11") (pintype "power_in"))
      (node (ref "IC5") (pin "16") (pinfunction "2~{OE}_16") (pintype "input"))
      (node (ref "IC55") (pin "1") (pinfunction "GND_1") (pintype "power_in"))
      (node (ref "IC6") (pin "1") (pinfunction "1~{OE}_1") (pintype "input"))
      (node (ref "IC6") (pin "10") (pinfunction "GND_10") (pintype "power_in"))
      (node (ref "IC6") (pin "11") (pinfunction "GND_11") (pintype "power_in"))
      (node (ref "IC6") (pin "16") (pinfunction "2~{OE}_16") (pintype "input"))
      (node (ref "IC6") (pin "5") (pinfunction "2DIR_5") (pintype "input"))
      (node (ref "IC7") (pin "1") (pinfunction "1~{OE}_1") (pintype "input"))
      (node (ref "IC7") (pin "10") (pinfunction "GND_10") (pintype "power_in"))
      (node (ref "IC7") (pin "11") (pinfunction "GND_11") (pintype "power_in"))
      (node (ref "IC7") (pin "16") (pinfunction "2~{OE}_16") (pintype "input"))
      (node (ref "IC8") (pin "1") (pinfunction "1~{OE}_1") (pintype "input"))
      (node (ref "IC8") (pin "10") (pinfunction "GND_10") (pintype "power_in"))
      (node (ref "IC8") (pin "11") (pinfunction "GND_11") (pintype "power_in"))
      (node (ref "IC8") (pin "16") (pinfunction "2~{OE}_16") (pintype "input"))
      (node (ref "IC8") (pin "5") (pinfunction "2DIR_5") (pintype "input"))
      (node (ref "IC9") (pin "1") (pinfunction "1~{OE}_1") (pintype "input"))
      (node (ref "IC9") (pin "10") (pinfunction "GND_10") (pintype "power_in"))
      (node (ref "IC9") (pin "11") (pinfunction "GND_11") (pintype "power_in"))
      (node (ref "IC9") (pin "16") (pinfunction "2~{OE}_16") (pintype "input"))
      (node (ref "IC9") (pin "4") (pinfunction "1DIR_4") (pintype "input"))
    )
    (net (code "67") (name "Net-(IC55-EN)") (class "Default")
      (node (ref "C295") (pin "1") (pinfunction "1_1") (pintype "passive"))
      (node (ref "IC55") (pin "7") (pinfunction "VREF2_7") (pintype "input"))
      (node (ref "IC55") (pin "8") (pinfunction "EN_8") (pintype "input"))
      (node (ref "R160") (pin "1") (pinfunction "1_1") (pintype "passive"))
    )
    (net (code "68") (name "P1V8") (class "Default")
      (node (ref "C290") (pin "1") (pinfunction "1_1") (pintype "passive"))
      (node (ref "C292") (pin "1") (pinfunction "1_1") (pintype "passive"))
      (node (ref "C298") (pin "1") (pinfunction "1_1") (pintype "passive"))
      (node (ref "IC1") (pin "2") (pinfunction "VCCB_2") (pintype "power_in"))
      (node (ref "IC3") (pin "2") (pinfunction "VCCB_2") (pintype "power_in"))
      (node (ref "IC7") (pin "2") (pinfunction "VCCB_2") (pintype "power_in"))
    )
    (net (code "69") (name "P3V3A") (class "Default")
      (node (ref "C115") (pin "1") (pinfunction "1_1") (pintype "passive"))
      (node (ref "C288") (pin "1") (pinfunction "1_1") (pintype "passive"))
      (node (ref "C296") (pin "1") (pinfunction "1_1") (pintype "passive"))
      (node (ref "C301") (pin "1") (pinfunction "1_1") (pintype "passive"))
      (node (ref "C303") (pin "1") (pinfunction "1_1") (pintype "passive"))
      (node (ref "C305") (pin "1") (pinfunction "1_1") (pintype "passive"))
      (node (ref "IC2") (pin "2") (pinfunction "VCCB_2") (pintype "power_in"))
      (node (ref "IC4") (pin "2") (pinfunction "VCCB_2") (pintype "power_in"))
      (node (ref "IC5") (pin "2") (pinfunction "VCCB_2") (pintype "power_in"))
      (node (ref "IC6") (pin "2") (pinfunction "VCCB_2") (pintype "power_in"))
      (node (ref "IC8") (pin "2") (pinfunction "VCCB_2") (pintype "power_in"))
      (node (ref "IC9") (pin "2") (pinfunction "VCCB_2") (pintype "power_in"))
      (node (ref "R160") (pin "2") (pinfunction "2_2") (pintype "passive"))
      (node (ref "R161") (pin "2") (pinfunction "2_2") (pintype "passive"))
      (node (ref "R162") (pin "2") (pinfunction "2_2") (pintype "passive"))
    )
    (net (code "70") (name "VADJ") (class "Default")
      (node (ref "C289") (pin "1") (pinfunction "1_1") (pintype "passive"))
      (node (ref "C291") (pin "1") (pinfunction "1_1") (pintype "passive"))
      (node (ref "C293") (pin "1") (pinfunction "1_1") (pintype "passive"))
      (node (ref "C294") (pin "2") (pinfunction "2_2") (pintype "passive"))
      (node (ref "C297") (pin "1") (pinfunction "1_1") (pintype "passive"))
      (node (ref "C299") (pin "1") (pinfunction "1_1") (pintype "passive"))
      (node (ref "C300") (pin "1") (pinfunction "1_1") (pintype "passive"))
      (node (ref "C302") (pin "1") (pinfunction "1_1") (pintype "passive"))
      (node (ref "C304") (pin "1") (pinfunction "1_1") (pintype "passive"))
      (node (ref "C306") (pin "1") (pinfunction "1_1") (pintype "passive"))
      (node (ref "IC1") (pin "3") (pinfunction "VCCA_3") (pintype "power_in"))
      (node (ref "IC1") (pin "5") (pinfunction "2DIR_5") (pintype "input"))
      (node (ref "IC2") (pin "3") (pinfunction "VCCA_3") (pintype "power_in"))
      (node (ref "IC2") (pin "5") (pinfunction "2DIR_5") (pintype "input"))
      (node (ref "IC3") (pin "3") (pinfunction "VCCA_3") (pintype "power_in"))
      (node (ref "IC3") (pin "4") (pinfunction "1DIR_4") (pintype "input"))
      (node (ref "IC3") (pin "5") (pinfunction "2DIR_5") (pintype "input"))
      (node (ref "IC4") (pin "3") (pinfunction "VCCA_3") (pintype "power_in"))
      (node (ref "IC4") (pin "5") (pinfunction "2DIR_5") (pintype "input"))
      (node (ref "IC5") (pin "3") (pinfunction "VCCA_3") (pintype "power_in"))
      (node (ref "IC5") (pin "4") (pinfunction "1DIR_4") (pintype "input"))
      (node (ref "IC5") (pin "5") (pinfunction "2DIR_5") (pintype "input"))
      (node (ref "IC55") (pin "2") (pinfunction "VREF1_2") (pintype "input"))
      (node (ref "IC6") (pin "3") (pinfunction "VCCA_3") (pintype "power_in"))
      (node (ref "IC6") (pin "4") (pinfunction "1DIR_4") (pintype "input"))
      (node (ref "IC7") (pin "3") (pinfunction "VCCA_3") (pintype "power_in"))
      (node (ref "IC7") (pin "4") (pinfunction "1DIR_4") (pintype "input"))
      (node (ref "IC7") (pin "5") (pinfunction "2DIR_5") (pintype "input"))
      (node (ref "IC8") (pin "3") (pinfunction "VCCA_3") (pintype "power_in"))
      (node (ref "IC8") (pin "4") (pinfunction "1DIR_4") (pintype "input"))
      (node (ref "IC9") (pin "3") (pinfunction "VCCA_3") (pintype "power_in"))
      (node (ref "IC9") (pin "5") (pinfunction "2DIR_5") (pintype "input"))
      (node (ref "R158") (pin "2") (pinfunction "2_2") (pintype "passive"))
      (node (ref "R159") (pin "2") (pinfunction "2_2") (pintype "passive"))
    )
    (net (code "71") (name "unconnected-(IC1-1A2-Pad7)") (class "Default")
      (node (ref "IC1") (pin "7") (pinfunction "1A2_7") (pintype "bidirectional+no_connect"))
    )
    (net (code "72") (name "unconnected-(IC1-1B2-Pad14)") (class "Default")
      (node (ref "IC1") (pin "14") (pinfunction "1B2_14") (pintype "bidirectional+no_connect"))
    )
    (net (code "73") (name "unconnected-(IC2-2A1-Pad8)") (class "Default")
      (node (ref "IC2") (pin "8") (pinfunction "2A1_8") (pintype "bidirectional+no_connect"))
    )
    (net (code "74") (name "unconnected-(IC2-2B1-Pad13)") (class "Default")
      (node (ref "IC2") (pin "13") (pinfunction "2B1_13") (pintype "bidirectional+no_connect"))
    )
    (net (code "75") (name "unconnected-(IC2-GND-Pad11)") (class "Default")
      (node (ref "IC2") (pin "11") (pinfunction "GND_11") (pintype "power_in"))
    )
    (net (code "76") (name "unconnected-(IC3-1A2-Pad7)") (class "Default")
      (node (ref "IC3") (pin "7") (pinfunction "1A2_7") (pintype "bidirectional+no_connect"))
    )
    (net (code "77") (name "unconnected-(IC3-1B2-Pad14)") (class "Default")
      (node (ref "IC3") (pin "14") (pinfunction "1B2_14") (pintype "bidirectional+no_connect"))
    )
    (net (code "78") (name "unconnected-(IC5-2A2-Pad9)") (class "Default")
      (node (ref "IC5") (pin "9") (pinfunction "2A2_9") (pintype "bidirectional+no_connect"))
    )
    (net (code "79") (name "unconnected-(IC5-2B2-Pad12)") (class "Default")
      (node (ref "IC5") (pin "12") (pinfunction "2B2_12") (pintype "bidirectional+no_connect"))
    )
    (net (code "80") (name "unconnected-(IC6-1A2-Pad7)") (class "Default")
      (node (ref "IC6") (pin "7") (pinfunction "1A2_7") (pintype "bidirectional+no_connect"))
    )
    (net (code "81") (name "unconnected-(IC6-1B2-Pad14)") (class "Default")
      (node (ref "IC6") (pin "14") (pinfunction "1B2_14") (pintype "bidirectional+no_connect"))
    )
    (net (code "82") (name "unconnected-(IC7-2A1-Pad8)") (class "Default")
      (node (ref "IC7") (pin "8") (pinfunction "2A1_8") (pintype "bidirectional+no_connect"))
    )
    (net (code "83") (name "unconnected-(IC7-2A2-Pad9)") (class "Default")
      (node (ref "IC7") (pin "9") (pinfunction "2A2_9") (pintype "bidirectional+no_connect"))
    )
    (net (code "84") (name "unconnected-(IC7-2B1-Pad13)") (class "Default")
      (node (ref "IC7") (pin "13") (pinfunction "2B1_13") (pintype "bidirectional+no_connect"))
    )
    (net (code "85") (name "unconnected-(IC7-2B2-Pad12)") (class "Default")
      (node (ref "IC7") (pin "12") (pinfunction "2B2_12") (pintype "bidirectional+no_connect"))
    )
    (net (code "86") (name "unconnected-(IC9-1A1-Pad6)") (class "Default")
      (node (ref "IC9") (pin "6") (pinfunction "1A1_6") (pintype "bidirectional+no_connect"))
    )
    (net (code "87") (name "unconnected-(IC9-1B1-Pad15)") (class "Default")
      (node (ref "IC9") (pin "15") (pinfunction "1B1_15") (pintype "bidirectional+no_connect"))
    )
  )
)
